# IO.net
KiCad netlist of a schematic drawn in Altium Designer
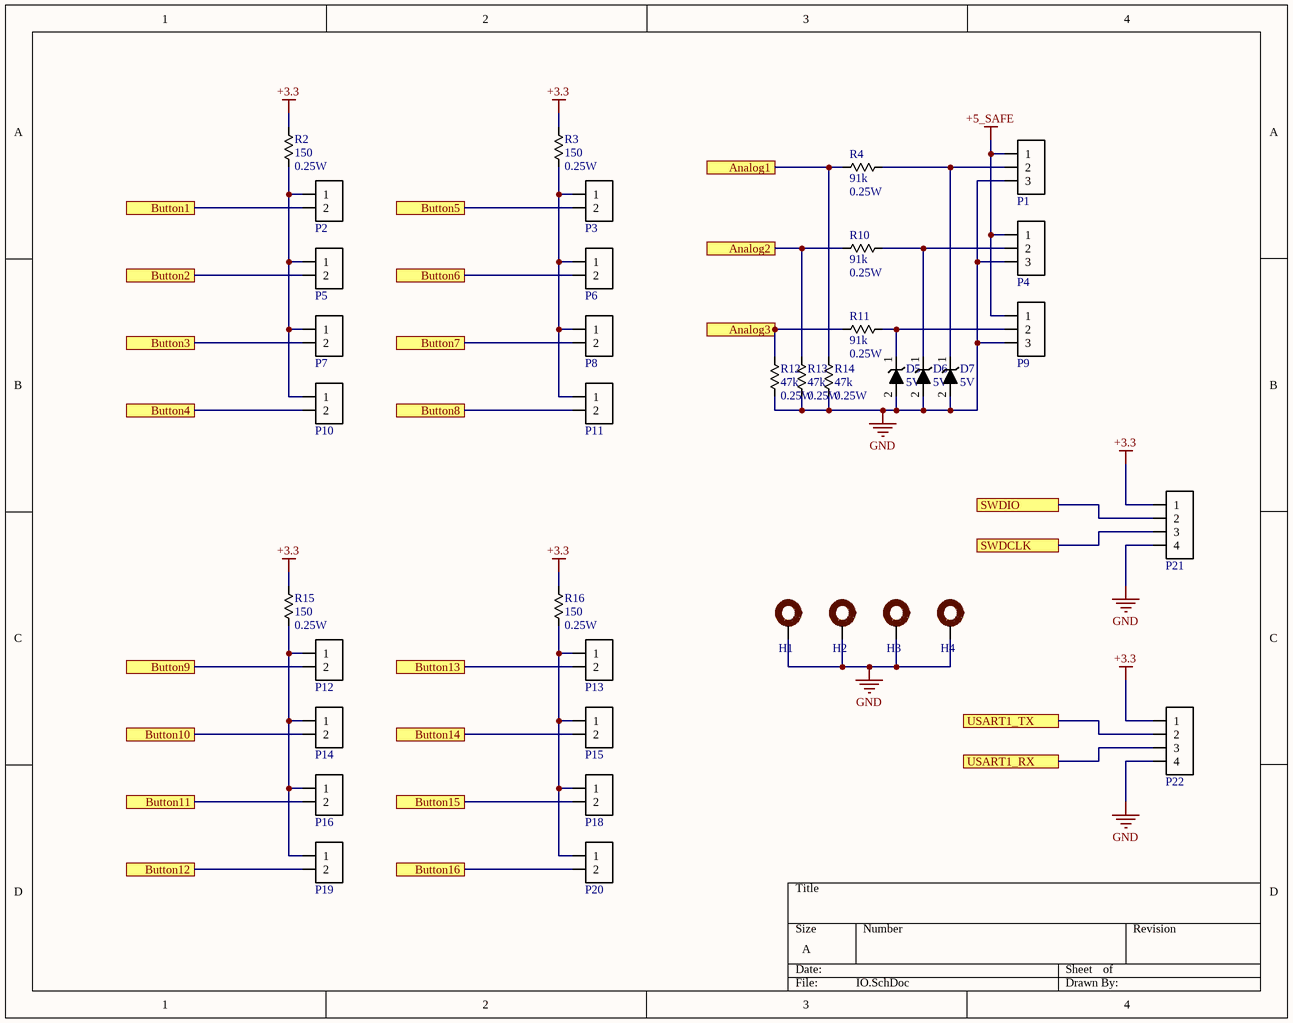
[diagram p0: IO.SchDoc]

(export (version "E")
  (design (tool "Eeschema 10.0.6"))
  (components
    (comp (ref "D5")
      (value "diode_1")
      (footprint "sod323_0")
      (description "TVS, 5V, 500W, SOD-323")
      (fields
        (field (name "REVERSE BREAKDOWN VOLTAGE") "5V")
        (field (name "PART NUMBER") "DIO-00037")
        (field (name "MANUFACTURER") "ST")
      )
      (libsource (lib "Diodes") (part "diode_1"))
    )
    (comp (ref "D6")
      (value "diode_1")
      (footprint "sod323_0")
      (description "TVS, 5V, 500W, SOD-323")
      (fields
        (field (name "REVERSE BREAKDOWN VOLTAGE") "5V")
        (field (name "PART NUMBER") "DIO-00037")
        (field (name "MANUFACTURER") "ST")
      )
      (libsource (lib "Diodes") (part "diode_1"))
    )
    (comp (ref "D7")
      (value "diode_1")
      (footprint "sod323_0")
      (description "TVS, 5V, 500W, SOD-323")
      (fields
        (field (name "REVERSE BREAKDOWN VOLTAGE") "5V")
        (field (name "PART NUMBER") "DIO-00037")
        (field (name "MANUFACTURER") "ST")
      )
      (libsource (lib "Diodes") (part "diode_1"))
    )
    (comp (ref "H1")
      (value "mounting_hole_0")
      (footprint "#8-32_SOCKET_HEAD")
      (description "#8-32 Mounting Hole for Socket Head Cap Screw")
      (fields (field (name "PART NUMBER") "MISC-00027"))
      (libsource (lib "Misc") (part "mounting_hole_0"))
    )
    (comp (ref "H2")
      (value "mounting_hole_0")
      (footprint "#8-32_SOCKET_HEAD")
      (description "#8-32 Mounting Hole for Socket Head Cap Screw")
      (fields (field (name "PART NUMBER") "MISC-00027"))
      (libsource (lib "Misc") (part "mounting_hole_0"))
    )
    (comp (ref "H3")
      (value "mounting_hole_0")
      (footprint "#8-32_SOCKET_HEAD")
      (description "#8-32 Mounting Hole for Socket Head Cap Screw")
      (fields (field (name "PART NUMBER") "MISC-00027"))
      (libsource (lib "Misc") (part "mounting_hole_0"))
    )
    (comp (ref "H4")
      (value "mounting_hole_0")
      (footprint "#8-32_SOCKET_HEAD")
      (description "#8-32 Mounting Hole for Socket Head Cap Screw")
      (fields (field (name "PART NUMBER") "MISC-00027"))
      (libsource (lib "Misc") (part "mounting_hole_0"))
    )
    (comp (ref "P1")
      (value "conn-3x1_0")
      (footprint "JST_PHR_3_0")
      (description "JST PH 3x1, THT, 2.00mm Pitch")
      (fields (field (name "PART NUMBER") "CONN-00047") (field (name "MANUFACTURER") "JST"))
      (libsource (lib "Connectors") (part "conn-3x1_0"))
    )
    (comp (ref "P2")
      (value "conn-2x1_0")
      (footprint "JST_PHR_2_0")
      (description "JST PH 2x1, THT, 2.00mm Pitch")
      (fields (field (name "PART NUMBER") "CONN-00048") (field (name "MANUFACTURER") "JST"))
      (libsource (lib "Connectors") (part "conn-2x1_0"))
    )
    (comp (ref "P3")
      (value "conn-2x1_0")
      (footprint "JST_PHR_2_0")
      (description "JST PH 2x1, THT, 2.00mm Pitch")
      (fields (field (name "PART NUMBER") "CONN-00048") (field (name "MANUFACTURER") "JST"))
      (libsource (lib "Connectors") (part "conn-2x1_0"))
    )
    (comp (ref "P4")
      (value "conn-3x1_0")
      (footprint "JST_PHR_3_0")
      (description "JST PH 3x1, THT, 2.00mm Pitch")
      (fields (field (name "PART NUMBER") "CONN-00047") (field (name "MANUFACTURER") "JST"))
      (libsource (lib "Connectors") (part "conn-3x1_0"))
    )
    (comp (ref "P5")
      (value "conn-2x1_0")
      (footprint "JST_PHR_2_0")
      (description "JST PH 2x1, THT, 2.00mm Pitch")
      (fields (field (name "PART NUMBER") "CONN-00048") (field (name "MANUFACTURER") "JST"))
      (libsource (lib "Connectors") (part "conn-2x1_0"))
    )
    (comp (ref "P6")
      (value "conn-2x1_0")
      (footprint "JST_PHR_2_0")
      (description "JST PH 2x1, THT, 2.00mm Pitch")
      (fields (field (name "PART NUMBER") "CONN-00048") (field (name "MANUFACTURER") "JST"))
      (libsource (lib "Connectors") (part "conn-2x1_0"))
    )
    (comp (ref "P7")
      (value "conn-2x1_0")
      (footprint "JST_PHR_2_0")
      (description "JST PH 2x1, THT, 2.00mm Pitch")
      (fields (field (name "PART NUMBER") "CONN-00048") (field (name "MANUFACTURER") "JST"))
      (libsource (lib "Connectors") (part "conn-2x1_0"))
    )
    (comp (ref "P8")
      (value "conn-2x1_0")
      (footprint "JST_PHR_2_0")
      (description "JST PH 2x1, THT, 2.00mm Pitch")
      (fields (field (name "PART NUMBER") "CONN-00048") (field (name "MANUFACTURER") "JST"))
      (libsource (lib "Connectors") (part "conn-2x1_0"))
    )
    (comp (ref "P9")
      (value "conn-3x1_0")
      (footprint "JST_PHR_3_0")
      (description "JST PH 3x1, THT, 2.00mm Pitch")
      (fields (field (name "PART NUMBER") "CONN-00047") (field (name "MANUFACTURER") "JST"))
      (libsource (lib "Connectors") (part "conn-3x1_0"))
    )
    (comp (ref "P10")
      (value "conn-2x1_0")
      (footprint "JST_PHR_2_0")
      (description "JST PH 2x1, THT, 2.00mm Pitch")
      (fields (field (name "PART NUMBER") "CONN-00048") (field (name "MANUFACTURER") "JST"))
      (libsource (lib "Connectors") (part "conn-2x1_0"))
    )
    (comp (ref "P11")
      (value "conn-2x1_0")
      (footprint "JST_PHR_2_0")
      (description "JST PH 2x1, THT, 2.00mm Pitch")
      (fields (field (name "PART NUMBER") "CONN-00048") (field (name "MANUFACTURER") "JST"))
      (libsource (lib "Connectors") (part "conn-2x1_0"))
    )
    (comp (ref "P12")
      (value "conn-2x1_0")
      (footprint "JST_PHR_2_0")
      (description "JST PH 2x1, THT, 2.00mm Pitch")
      (fields (field (name "PART NUMBER") "CONN-00048") (field (name "MANUFACTURER") "JST"))
      (libsource (lib "Connectors") (part "conn-2x1_0"))
    )
    (comp (ref "P13")
      (value "conn-2x1_0")
      (footprint "JST_PHR_2_0")
      (description "JST PH 2x1, THT, 2.00mm Pitch")
      (fields (field (name "PART NUMBER") "CONN-00048") (field (name "MANUFACTURER") "JST"))
      (libsource (lib "Connectors") (part "conn-2x1_0"))
    )
    (comp (ref "P14")
      (value "conn-2x1_0")
      (footprint "JST_PHR_2_0")
      (description "JST PH 2x1, THT, 2.00mm Pitch")
      (fields (field (name "PART NUMBER") "CONN-00048") (field (name "MANUFACTURER") "JST"))
      (libsource (lib "Connectors") (part "conn-2x1_0"))
    )
    (comp (ref "P15")
      (value "conn-2x1_0")
      (footprint "JST_PHR_2_0")
      (description "JST PH 2x1, THT, 2.00mm Pitch")
      (fields (field (name "PART NUMBER") "CONN-00048") (field (name "MANUFACTURER") "JST"))
      (libsource (lib "Connectors") (part "conn-2x1_0"))
    )
    (comp (ref "P16")
      (value "conn-2x1_0")
      (footprint "JST_PHR_2_0")
      (description "JST PH 2x1, THT, 2.00mm Pitch")
      (fields (field (name "PART NUMBER") "CONN-00048") (field (name "MANUFACTURER") "JST"))
      (libsource (lib "Connectors") (part "conn-2x1_0"))
    )
    (comp (ref "P18")
      (value "conn-2x1_0")
      (footprint "JST_PHR_2_0")
      (description "JST PH 2x1, THT, 2.00mm Pitch")
      (fields (field (name "PART NUMBER") "CONN-00048") (field (name "MANUFACTURER") "JST"))
      (libsource (lib "Connectors") (part "conn-2x1_0"))
    )
    (comp (ref "P19")
      (value "conn-2x1_0")
      (footprint "JST_PHR_2_0")
      (description "JST PH 2x1, THT, 2.00mm Pitch")
      (fields (field (name "PART NUMBER") "CONN-00048") (field (name "MANUFACTURER") "JST"))
      (libsource (lib "Connectors") (part "conn-2x1_0"))
    )
    (comp (ref "P20")
      (value "conn-2x1_0")
      (footprint "JST_PHR_2_0")
      (description "JST PH 2x1, THT, 2.00mm Pitch")
      (fields (field (name "PART NUMBER") "CONN-00048") (field (name "MANUFACTURER") "JST"))
      (libsource (lib "Connectors") (part "conn-2x1_0"))
    )
    (comp (ref "P21")
      (value "conn-4x1_0")
      (footprint "HDDR_4x1_0")
      (description "Header 4x1, 0.1\"")
      (fields (field (name "PART NUMBER") "CONN-00029"))
      (libsource (lib "Connectors") (part "conn-4x1_0"))
    )
    (comp (ref "P22")
      (value "conn-4x1_0")
      (footprint "HDDR_4x1_0")
      (description "Header 4x1, 0.1\"")
      (fields (field (name "PART NUMBER") "CONN-00029"))
      (libsource (lib "Connectors") (part "conn-4x1_0"))
    )
    (comp (ref "R2")
      (value "res_single")
      (footprint "chip_0603")
      (description "RES SMD 150 OHM 1% 1/4W 0603")
      (fields
        (field (name "TOLERANCE") "1%")
        (field (name "RESISTANCE") "150")
        (field (name "POWER RATING") "0.25W")
        (field (name "PART NUMBER") "RES-00188")
      )
      (libsource (lib "Resistors") (part "res_single"))
    )
    (comp (ref "R3")
      (value "res_single")
      (footprint "chip_0603")
      (description "RES SMD 150 OHM 1% 1/4W 0603")
      (fields
        (field (name "TOLERANCE") "1%")
        (field (name "RESISTANCE") "150")
        (field (name "POWER RATING") "0.25W")
        (field (name "PART NUMBER") "RES-00188")
      )
      (libsource (lib "Resistors") (part "res_single"))
    )
    (comp (ref "R4")
      (value "res_single")
      (footprint "chip_0603")
      (description "RES SMD 91K OHM 1% 1/4W 0603")
      (fields
        (field (name "TOLERANCE") "1%")
        (field (name "RESISTANCE") "91k")
        (field (name "POWER RATING") "0.25W")
        (field (name "PART NUMBER") "RES-00586")
      )
      (libsource (lib "Resistors") (part "res_single"))
    )
    (comp (ref "R10")
      (value "res_single")
      (footprint "chip_0603")
      (description "RES SMD 91K OHM 1% 1/4W 0603")
      (fields
        (field (name "TOLERANCE") "1%")
        (field (name "RESISTANCE") "91k")
        (field (name "POWER RATING") "0.25W")
        (field (name "PART NUMBER") "RES-00586")
      )
      (libsource (lib "Resistors") (part "res_single"))
    )
    (comp (ref "R11")
      (value "res_single")
      (footprint "chip_0603")
      (description "RES SMD 91K OHM 1% 1/4W 0603")
      (fields
        (field (name "TOLERANCE") "1%")
        (field (name "RESISTANCE") "91k")
        (field (name "POWER RATING") "0.25W")
        (field (name "PART NUMBER") "RES-00586")
      )
      (libsource (lib "Resistors") (part "res_single"))
    )
    (comp (ref "R12")
      (value "res_single")
      (footprint "chip_0603")
      (description "RES SMD 47K OHM 1% 1/4W 0603")
      (fields
        (field (name "TOLERANCE") "1%")
        (field (name "RESISTANCE") "47k")
        (field (name "POWER RATING") "0.25W")
        (field (name "PART NUMBER") "RES-00492")
      )
      (libsource (lib "Resistors") (part "res_single"))
    )
    (comp (ref "R13")
      (value "res_single")
      (footprint "chip_0603")
      (description "RES SMD 47K OHM 1% 1/4W 0603")
      (fields
        (field (name "TOLERANCE") "1%")
        (field (name "RESISTANCE") "47k")
        (field (name "POWER RATING") "0.25W")
        (field (name "PART NUMBER") "RES-00492")
      )
      (libsource (lib "Resistors") (part "res_single"))
    )
    (comp (ref "R14")
      (value "res_single")
      (footprint "chip_0603")
      (description "RES SMD 47K OHM 1% 1/4W 0603")
      (fields
        (field (name "TOLERANCE") "1%")
        (field (name "RESISTANCE") "47k")
        (field (name "POWER RATING") "0.25W")
        (field (name "PART NUMBER") "RES-00492")
      )
      (libsource (lib "Resistors") (part "res_single"))
    )
    (comp (ref "R15")
      (value "res_single")
      (footprint "chip_0603")
      (description "RES SMD 150 OHM 1% 1/4W 0603")
      (fields
        (field (name "TOLERANCE") "1%")
        (field (name "RESISTANCE") "150")
        (field (name "POWER RATING") "0.25W")
        (field (name "PART NUMBER") "RES-00188")
      )
      (libsource (lib "Resistors") (part "res_single"))
    )
    (comp (ref "R16")
      (value "res_single")
      (footprint "chip_0603")
      (description "RES SMD 150 OHM 1% 1/4W 0603")
      (fields
        (field (name "TOLERANCE") "1%")
        (field (name "RESISTANCE") "150")
        (field (name "POWER RATING") "0.25W")
        (field (name "PART NUMBER") "RES-00188")
      )
      (libsource (lib "Resistors") (part "res_single"))
    )
  )
  (nets
    (net (code "1") (name "+3.3") (class "Default")
      (node (ref "P21") (pin "1") (pinfunction "1_1") (pintype "passive"))
      (node (ref "P22") (pin "1") (pinfunction "1_1") (pintype "passive"))
      (node (ref "R15") (pin "2") (pinfunction "2_2") (pintype "passive"))
      (node (ref "R16") (pin "2") (pinfunction "2_2") (pintype "passive"))
      (node (ref "R2") (pin "2") (pinfunction "2_2") (pintype "passive"))
      (node (ref "R3") (pin "2") (pinfunction "2_2") (pintype "passive"))
    )
    (net (code "2") (name "+5_SAFE") (class "Default")
      (node (ref "P1") (pin "1") (pinfunction "1_1") (pintype "passive"))
      (node (ref "P4") (pin "1") (pinfunction "1_1") (pintype "passive"))
      (node (ref "P9") (pin "1") (pinfunction "1_1") (pintype "passive"))
    )
    (net (code "3") (name "/Analog1") (class "Default")
      (node (ref "R14") (pin "1") (pinfunction "1_1") (pintype "passive"))
      (node (ref "R4") (pin "1") (pinfunction "1_1") (pintype "passive"))
    )
    (net (code "4") (name "/Analog2") (class "Default")
      (node (ref "R10") (pin "1") (pinfunction "1_1") (pintype "passive"))
      (node (ref "R13") (pin "1") (pinfunction "1_1") (pintype "passive"))
    )
    (net (code "5") (name "/Analog3") (class "Default")
      (node (ref "R11") (pin "1") (pinfunction "1_1") (pintype "passive"))
      (node (ref "R12") (pin "1") (pinfunction "1_1") (pintype "passive"))
    )
    (net (code "6") (name "/Button1") (class "Default")
      (node (ref "P2") (pin "2") (pinfunction "2_2") (pintype "passive"))
    )
    (net (code "7") (name "/Button2") (class "Default")
      (node (ref "P5") (pin "2") (pinfunction "2_2") (pintype "passive"))
    )
    (net (code "8") (name "/Button3") (class "Default")
      (node (ref "P7") (pin "2") (pinfunction "2_2") (pintype "passive"))
    )
    (net (code "9") (name "/Button4") (class "Default")
      (node (ref "P10") (pin "2") (pinfunction "2_2") (pintype "passive"))
    )
    (net (code "10") (name "/Button5") (class "Default")
      (node (ref "P3") (pin "2") (pinfunction "2_2") (pintype "passive"))
    )
    (net (code "11") (name "/Button6") (class "Default")
      (node (ref "P6") (pin "2") (pinfunction "2_2") (pintype "passive"))
    )
    (net (code "12") (name "/Button7") (class "Default")
      (node (ref "P8") (pin "2") (pinfunction "2_2") (pintype "passive"))
    )
    (net (code "13") (name "/Button8") (class "Default")
      (node (ref "P11") (pin "2") (pinfunction "2_2") (pintype "passive"))
    )
    (net (code "14") (name "/Button9") (class "Default")
      (node (ref "P12") (pin "2") (pinfunction "2_2") (pintype "passive"))
    )
    (net (code "15") (name "/Button10") (class "Default")
      (node (ref "P14") (pin "2") (pinfunction "2_2") (pintype "passive"))
    )
    (net (code "16") (name "/Button11") (class "Default")
      (node (ref "P16") (pin "2") (pinfunction "2_2") (pintype "passive"))
    )
    (net (code "17") (name "/Button12") (class "Default")
      (node (ref "P19") (pin "2") (pinfunction "2_2") (pintype "passive"))
    )
    (net (code "18") (name "/Button13") (class "Default")
      (node (ref "P13") (pin "2") (pinfunction "2_2") (pintype "passive"))
    )
    (net (code "19") (name "/Button14") (class "Default")
      (node (ref "P15") (pin "2") (pinfunction "2_2") (pintype "passive"))
    )
    (net (code "20") (name "/Button15") (class "Default")
      (node (ref "P18") (pin "2") (pinfunction "2_2") (pintype "passive"))
    )
    (net (code "21") (name "/Button16") (class "Default")
      (node (ref "P20") (pin "2") (pinfunction "2_2") (pintype "passive"))
    )
    (net (code "22") (name "/SWDCLK") (class "Default")
      (node (ref "P21") (pin "3") (pinfunction "3_3") (pintype "passive"))
    )
    (net (code "23") (name "/SWDIO") (class "Default")
      (node (ref "P21") (pin "2") (pinfunction "2_2") (pintype "passive"))
    )
    (net (code "24") (name "/USART1_RX") (class "Default")
      (node (ref "P22") (pin "3") (pinfunction "3_3") (pintype "passive"))
    )
    (net (code "25") (name "/USART1_TX") (class "Default")
      (node (ref "P22") (pin "2") (pinfunction "2_2") (pintype "passive"))
    )
    (net (code "26") (name "GND") (class "Default")
      (node (ref "D5") (pin "2") (pinfunction "2_2") (pintype "passive"))
      (node (ref "D6") (pin "2") (pinfunction "2_2") (pintype "passive"))
      (node (ref "D7") (pin "2") (pinfunction "2_2") (pintype "passive"))
      (node (ref "H1") (pin "0") (pinfunction "A_0") (pintype "passive"))
      (node (ref "H2") (pin "0") (pinfunction "A_0") (pintype "passive"))
      (node (ref "H3") (pin "0") (pinfunction "A_0") (pintype "passive"))
      (node (ref "H4") (pin "0") (pinfunction "A_0") (pintype "passive"))
      (node (ref "P1") (pin "3") (pinfunction "3_3") (pintype "passive"))
      (node (ref "P21") (pin "4") (pinfunction "4_4") (pintype "passive"))
      (node (ref "P22") (pin "4") (pinfunction "4_4") (pintype "passive"))
      (node (ref "P4") (pin "3") (pinfunction "3_3") (pintype "passive"))
      (node (ref "P9") (pin "3") (pinfunction "3_3") (pintype "passive"))
      (node (ref "R12") (pin "2") (pinfunction "2_2") (pintype "passive"))
      (node (ref "R13") (pin "2") (pinfunction "2_2") (pintype "passive"))
      (node (ref "R14") (pin "2") (pinfunction "2_2") (pintype "passive"))
    )
    (net (code "27") (name "Net-(D5-Pad1)") (class "Default")
      (node (ref "D5") (pin "1") (pinfunction "1_1") (pintype "passive"))
      (node (ref "P9") (pin "2") (pinfunction "2_2") (pintype "passive"))
      (node (ref "R11") (pin "2") (pinfunction "2_2") (pintype "passive"))
    )
    (net (code "28") (name "Net-(D6-Pad1)") (class "Default")
      (node (ref "D6") (pin "1") (pinfunction "1_1") (pintype "passive"))
      (node (ref "P4") (pin "2") (pinfunction "2_2") (pintype "passive"))
      (node (ref "R10") (pin "2") (pinfunction "2_2") (pintype "passive"))
    )
    (net (code "29") (name "Net-(D7-Pad1)") (class "Default")
      (node (ref "D7") (pin "1") (pinfunction "1_1") (pintype "passive"))
      (node (ref "P1") (pin "2") (pinfunction "2_2") (pintype "passive"))
      (node (ref "R4") (pin "2") (pinfunction "2_2") (pintype "passive"))
    )
    (net (code "30") (name "Net-(P10-Pad1)") (class "Default")
      (node (ref "P10") (pin "1") (pinfunction "1_1") (pintype "passive"))
      (node (ref "P2") (pin "1") (pinfunction "1_1") (pintype "passive"))
      (node (ref "P5") (pin "1") (pinfunction "1_1") (pintype "passive"))
      (node (ref "P7") (pin "1") (pinfunction "1_1") (pintype "passive"))
      (node (ref "R2") (pin "1") (pinfunction "1_1") (pintype "passive"))
    )
    (net (code "31") (name "Net-(P11-Pad1)") (class "Default")
      (node (ref "P11") (pin "1") (pinfunction "1_1") (pintype "passive"))
      (node (ref "P3") (pin "1") (pinfunction "1_1") (pintype "passive"))
      (node (ref "P6") (pin "1") (pinfunction "1_1") (pintype "passive"))
      (node (ref "P8") (pin "1") (pinfunction "1_1") (pintype "passive"))
      (node (ref "R3") (pin "1") (pinfunction "1_1") (pintype "passive"))
    )
    (net (code "32") (name "Net-(P12-Pad1)") (class "Default")
      (node (ref "P12") (pin "1") (pinfunction "1_1") (pintype "passive"))
      (node (ref "P14") (pin "1") (pinfunction "1_1") (pintype "passive"))
      (node (ref "P16") (pin "1") (pinfunction "1_1") (pintype "passive"))
      (node (ref "P19") (pin "1") (pinfunction "1_1") (pintype "passive"))
      (node (ref "R15") (pin "1") (pinfunction "1_1") (pintype "passive"))
    )
    (net (code "33") (name "Net-(P13-Pad1)") (class "Default")
      (node (ref "P13") (pin "1") (pinfunction "1_1") (pintype "passive"))
      (node (ref "P15") (pin "1") (pinfunction "1_1") (pintype "passive"))
      (node (ref "P18") (pin "1") (pinfunction "1_1") (pintype "passive"))
      (node (ref "P20") (pin "1") (pinfunction "1_1") (pintype "passive"))
      (node (ref "R16") (pin "1") (pinfunction "1_1") (pintype "passive"))
    )
  )
)
